# 12mPCIe.net
KiCad netlist of a schematic drawn in Altium Designer
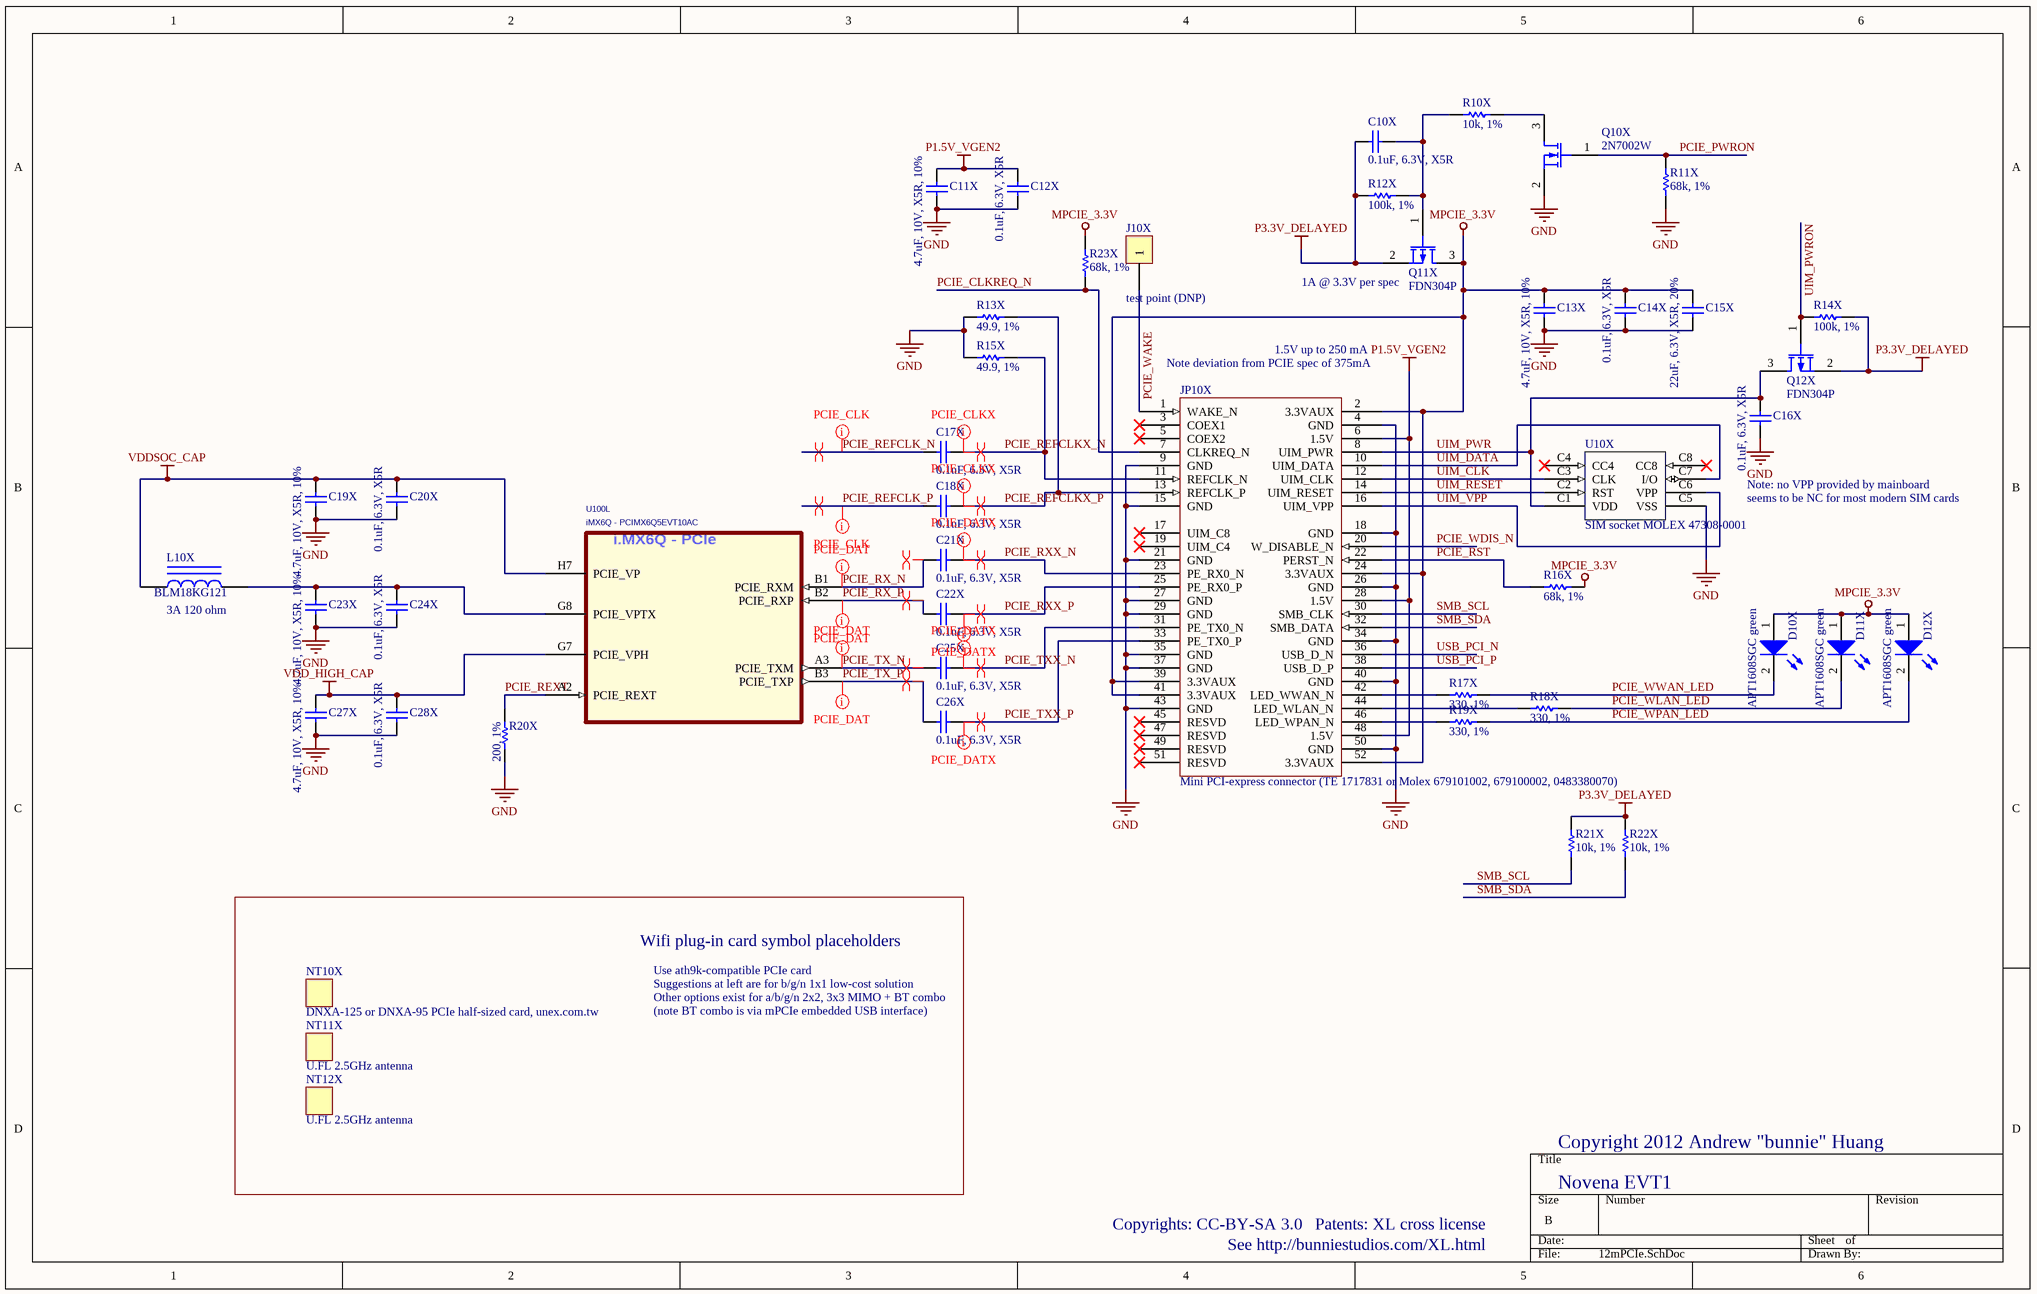
[diagram p0: 12mPCIe.SchDoc]

(export (version "E")
  (design (tool "Eeschema 10.0.6"))
  (components
    (comp (ref "C10X")
      (value "0.1uF, 6.3V, X5R")
      (footprint "CAPC0603N_B")
      (description "Capacitor (Semiconductor SIM Model)")
      (fields (field (name "PUBLISHER") "Altium Limited"))
      (libsource (lib "Miscellaneous Devices") (part "Cap Semi"))
    )
    (comp (ref "C11X")
      (value "4.7uF, 10V, X5R, 10%")
      (footprint "CAPC1608N")
      (description "Capacitor (Semiconductor SIM Model)")
      (fields (field (name "PUBLISHER") "Altium Limited"))
      (libsource (lib "Miscellaneous Devices") (part "Cap Semi"))
    )
    (comp (ref "C12X")
      (value "0.1uF, 6.3V, X5R")
      (footprint "CAPC0603N_B")
      (description "Capacitor (Semiconductor SIM Model)")
      (fields (field (name "PUBLISHER") "Altium Limited"))
      (libsource (lib "Miscellaneous Devices") (part "Cap Semi"))
    )
    (comp (ref "C13X")
      (value "4.7uF, 10V, X5R, 10%")
      (footprint "CAPC1608N")
      (description "Capacitor (Semiconductor SIM Model)")
      (fields (field (name "PUBLISHER") "Altium Limited"))
      (libsource (lib "Miscellaneous Devices") (part "Cap Semi"))
    )
    (comp (ref "C14X")
      (value "0.1uF, 6.3V, X5R")
      (footprint "CAPC0603N_B")
      (description "Capacitor (Semiconductor SIM Model)")
      (fields (field (name "PUBLISHER") "Altium Limited"))
      (libsource (lib "Miscellaneous Devices") (part "Cap Semi"))
    )
    (comp (ref "C15X")
      (value "22uF, 6.3V, X5R, 20%")
      (footprint "CAPC1608N_HD")
      (description "Capacitor (Semiconductor SIM Model)")
      (fields (field (name "PUBLISHER") "Altium Limited"))
      (libsource (lib "Miscellaneous Devices") (part "Cap Semi"))
    )
    (comp (ref "C16X")
      (value "0.1uF, 6.3V, X5R")
      (footprint "CAPC0603N_B")
      (description "Capacitor (Semiconductor SIM Model)")
      (fields (field (name "PUBLISHER") "Altium Limited"))
      (libsource (lib "Miscellaneous Devices") (part "Cap Semi"))
    )
    (comp (ref "C17X")
      (value "0.1uF, 6.3V, X5R")
      (footprint "CAPC0603N_B")
      (description "Capacitor (Semiconductor SIM Model)")
      (fields (field (name "PUBLISHER") "Altium Limited"))
      (libsource (lib "Miscellaneous Devices") (part "Cap Semi"))
    )
    (comp (ref "C18X")
      (value "0.1uF, 6.3V, X5R")
      (footprint "CAPC0603N_B")
      (description "Capacitor (Semiconductor SIM Model)")
      (fields (field (name "PUBLISHER") "Altium Limited"))
      (libsource (lib "Miscellaneous Devices") (part "Cap Semi"))
    )
    (comp (ref "C19X")
      (value "4.7uF, 10V, X5R, 10%")
      (footprint "CAPC1608N_HD")
      (description "Capacitor (Semiconductor SIM Model)")
      (fields (field (name "PUBLISHER") "Altium Limited"))
      (libsource (lib "Miscellaneous Devices") (part "Cap Semi"))
    )
    (comp (ref "C20X")
      (value "0.1uF, 6.3V, X5R")
      (footprint "CAPC0603N_B")
      (description "Capacitor (Semiconductor SIM Model)")
      (fields (field (name "PUBLISHER") "Altium Limited"))
      (libsource (lib "Miscellaneous Devices") (part "Cap Semi"))
    )
    (comp (ref "C21X")
      (value "0.1uF, 6.3V, X5R")
      (footprint "CAPC0603N_B")
      (description "Capacitor (Semiconductor SIM Model)")
      (fields (field (name "PUBLISHER") "Altium Limited"))
      (libsource (lib "Miscellaneous Devices") (part "Cap Semi"))
    )
    (comp (ref "C22X")
      (value "0.1uF, 6.3V, X5R")
      (footprint "CAPC0603N_B")
      (description "Capacitor (Semiconductor SIM Model)")
      (fields (field (name "PUBLISHER") "Altium Limited"))
      (libsource (lib "Miscellaneous Devices") (part "Cap Semi"))
    )
    (comp (ref "C23X")
      (value "4.7uF, 10V, X5R, 10%")
      (footprint "CAPC1608N_HD")
      (description "Capacitor (Semiconductor SIM Model)")
      (fields (field (name "PUBLISHER") "Altium Limited"))
      (libsource (lib "Miscellaneous Devices") (part "Cap Semi"))
    )
    (comp (ref "C24X")
      (value "0.1uF, 6.3V, X5R")
      (footprint "CAPC0603N_B")
      (description "Capacitor (Semiconductor SIM Model)")
      (fields (field (name "PUBLISHER") "Altium Limited"))
      (libsource (lib "Miscellaneous Devices") (part "Cap Semi"))
    )
    (comp (ref "C25X")
      (value "0.1uF, 6.3V, X5R")
      (footprint "CAPC0603N_B")
      (description "Capacitor (Semiconductor SIM Model)")
      (fields (field (name "PUBLISHER") "Altium Limited"))
      (libsource (lib "Miscellaneous Devices") (part "Cap Semi"))
    )
    (comp (ref "C26X")
      (value "0.1uF, 6.3V, X5R")
      (footprint "CAPC0603N_B")
      (description "Capacitor (Semiconductor SIM Model)")
      (fields (field (name "PUBLISHER") "Altium Limited"))
      (libsource (lib "Miscellaneous Devices") (part "Cap Semi"))
    )
    (comp (ref "C27X")
      (value "4.7uF, 10V, X5R, 10%")
      (footprint "CAPC1608N_HD")
      (description "Capacitor (Semiconductor SIM Model)")
      (fields (field (name "PUBLISHER") "Altium Limited"))
      (libsource (lib "Miscellaneous Devices") (part "Cap Semi"))
    )
    (comp (ref "C28X")
      (value "0.1uF, 6.3V, X5R")
      (footprint "CAPC0603N_B")
      (description "Capacitor (Semiconductor SIM Model)")
      (fields (field (name "PUBLISHER") "Altium Limited"))
      (libsource (lib "Miscellaneous Devices") (part "Cap Semi"))
    )
    (comp (ref "D10X")
      (value "APT1608SGC green")
      (footprint "CD1608-0603")
      (description "Typical RED, GREEN, YELLOW, AMBER GaAs LED")
      (fields (field (name "PUBLISHER") "Altium Limited"))
      (libsource (lib "Miscellaneous Devices") (part "LED2"))
    )
    (comp (ref "D11X")
      (value "APT1608SGC green")
      (footprint "CD1608-0603")
      (description "Typical RED, GREEN, YELLOW, AMBER GaAs LED")
      (fields (field (name "PUBLISHER") "Altium Limited"))
      (libsource (lib "Miscellaneous Devices") (part "LED2"))
    )
    (comp (ref "D12X")
      (value "APT1608SGC green")
      (footprint "CD1608-0603")
      (description "Typical RED, GREEN, YELLOW, AMBER GaAs LED")
      (fields (field (name "PUBLISHER") "Altium Limited"))
      (libsource (lib "Miscellaneous Devices") (part "LED2"))
    )
    (comp (ref "J10X")
      (value "test point (DNP)")
      (footprint "TP_SMT_38mil")
      (description "Connector")
      (libsource (lib "*") (part "CON1"))
    )
    (comp (ref "JP10X")
      (value "Mini PCI-express connector (TE 1717831 or Molex 679101002, 679100002, 0483380070)")
      (footprint "MPCI_FULL_TE_1717831")
      (description "Mini PCI-express, e.g. TE 1717831")
      (libsource (lib "commonsch") (part "MINI_PCIE"))
    )
    (comp (ref "L10X")
      (value "BLM18KG121")
      (footprint "INDC1608AN")
      (description "Magnetic-Core Inductor")
      (fields (field (name "ALTIUM_VALUE") "3A 120 ohm") (field (name "PUBLISHER") "Altium Limited"))
      (libsource (lib "Miscellaneous Devices") (part "Inductor Iron"))
    )
    (comp (ref "NT10X")
      (value "DNXA-125 or DNXA-95 PCIe half-sized card, unex.com.tw")
      (description "Placeholder for non-electrical BOM items")
      (libsource (lib "commonsch") (part "NOTE"))
    )
    (comp (ref "NT11X")
      (value "U.FL 2.5GHz antenna")
      (description "Placeholder for non-electrical BOM items")
      (libsource (lib "commonsch") (part "NOTE"))
    )
    (comp (ref "NT12X")
      (value "U.FL 2.5GHz antenna")
      (description "Placeholder for non-electrical BOM items")
      (libsource (lib "commonsch") (part "NOTE"))
    )
    (comp (ref "Q10X")
      (value "2N7002W")
      (footprint "SOT323-3AN")
      (description "N-Channel MOSFET")
      (fields (field (name "PUBLISHER") "Altium Limited"))
      (libsource (lib "Miscellaneous Devices") (part "MOSFET-N"))
    )
    (comp (ref "Q11X")
      (value "FDN304P")
      (footprint "SOT23-3N")
      (description "P-Channel MOSFET")
      (fields (field (name "PUBLISHER") "Altium Limited"))
      (libsource (lib "Miscellaneous Devices") (part "MOSFET-P"))
    )
    (comp (ref "Q12X")
      (value "FDN304P")
      (footprint "SOT23-3N")
      (description "P-Channel MOSFET")
      (fields (field (name "PUBLISHER") "Altium Limited"))
      (libsource (lib "Miscellaneous Devices") (part "MOSFET-P"))
    )
    (comp (ref "R10X")
      (value "10k, 1%")
      (footprint "RESC1005N")
      (description "Resistor")
      (fields (field (name "PUBLISHER") "Altium Limited"))
      (libsource (lib "Miscellaneous Devices") (part "Res1"))
    )
    (comp (ref "R11X")
      (value "68k, 1%")
      (footprint "RESC1005N")
      (description "Resistor")
      (fields (field (name "PUBLISHER") "Altium Limited"))
      (libsource (lib "Miscellaneous Devices") (part "Res1"))
    )
    (comp (ref "R12X")
      (value "100k, 1%")
      (footprint "RESC1005N")
      (description "Resistor")
      (fields (field (name "PUBLISHER") "Altium Limited"))
      (libsource (lib "Miscellaneous Devices") (part "Res1"))
    )
    (comp (ref "R13X")
      (value "49.9, 1%")
      (footprint "RESC1005N")
      (description "Resistor")
      (fields (field (name "PUBLISHER") "Altium Limited"))
      (libsource (lib "Miscellaneous Devices") (part "Res1"))
    )
    (comp (ref "R14X")
      (value "100k, 1%")
      (footprint "RESC1005N")
      (description "Resistor")
      (fields (field (name "PUBLISHER") "Altium Limited"))
      (libsource (lib "Miscellaneous Devices") (part "Res1"))
    )
    (comp (ref "R15X")
      (value "49.9, 1%")
      (footprint "RESC1005N")
      (description "Resistor")
      (fields (field (name "PUBLISHER") "Altium Limited"))
      (libsource (lib "Miscellaneous Devices") (part "Res1"))
    )
    (comp (ref "R16X")
      (value "68k, 1%")
      (footprint "RESC1005N")
      (description "Resistor")
      (fields (field (name "PUBLISHER") "Altium Limited"))
      (libsource (lib "Miscellaneous Devices") (part "Res1"))
    )
    (comp (ref "R17X")
      (value "330, 1%")
      (footprint "RESC1005N")
      (description "Resistor")
      (fields (field (name "PUBLISHER") "Altium Limited"))
      (libsource (lib "Miscellaneous Devices") (part "Res1"))
    )
    (comp (ref "R18X")
      (value "330, 1%")
      (footprint "RESC1005N")
      (description "Resistor")
      (fields (field (name "PUBLISHER") "Altium Limited"))
      (libsource (lib "Miscellaneous Devices") (part "Res1"))
    )
    (comp (ref "R19X")
      (value "330, 1%")
      (footprint "RESC1005N")
      (description "Resistor")
      (fields (field (name "PUBLISHER") "Altium Limited"))
      (libsource (lib "Miscellaneous Devices") (part "Res1"))
    )
    (comp (ref "R20X")
      (value "200, 1%")
      (footprint "RESC1005N")
      (description "Resistor")
      (fields (field (name "PUBLISHER") "Altium Limited"))
      (libsource (lib "Miscellaneous Devices") (part "Res1"))
    )
    (comp (ref "R21X")
      (value "10k, 1%")
      (footprint "RESC1005N")
      (description "Resistor")
      (fields (field (name "PUBLISHER") "Altium Limited"))
      (libsource (lib "Miscellaneous Devices") (part "Res1"))
    )
    (comp (ref "R22X")
      (value "10k, 1%")
      (footprint "RESC1005N")
      (description "Resistor")
      (fields (field (name "PUBLISHER") "Altium Limited"))
      (libsource (lib "Miscellaneous Devices") (part "Res1"))
    )
    (comp (ref "R23X")
      (value "68k, 1%")
      (footprint "RESC1005N")
      (description "Resistor")
      (fields (field (name "PUBLISHER") "Altium Limited"))
      (libsource (lib "Miscellaneous Devices") (part "Res1"))
    )
    (comp (ref "U10X")
      (value "SIM socket MOLEX 47308-0001")
      (footprint "MOLEX_SIM_47308-001")
      (description "ISO 7816 SIM card socket")
      (libsource (lib "commonsch") (part "ISO7816 (SIM card)"))
    )
    (comp (ref "U100")
      (value "iMX6Q - PCIMX6Q5EVT10AC")
      (description "PLACEHOLDER FOR FREESCALE PART NUMBER PMCIMX6Q6VV1A.")
      (libsource (lib "*") (part "PCIMX6Q6VV1A"))
    )
  )
  (nets
    (net (code "1") (name "/PCIE_CLKREQ_N") (class "Default")
      (node (ref "JP10X") (pin "7") (pinfunction "CLKREQ_N_7") (pintype "passive"))
      (node (ref "R23X") (pin "1") (pinfunction "1_1") (pintype "passive"))
    )
    (net (code "2") (name "/PCIE_PWRON") (class "Default")
      (node (ref "Q10X") (pin "1") (pinfunction "G_1") (pintype "passive"))
      (node (ref "R11X") (pin "1") (pinfunction "1_1") (pintype "passive"))
    )
    (net (code "3") (name "/PCIE_REFCLKX_N") (class "Default")
      (node (ref "C17X") (pin "1") (pinfunction "1_1") (pintype "passive"))
      (node (ref "JP10X") (pin "11") (pinfunction "REFCLK_N_11") (pintype "input"))
      (node (ref "R15X") (pin "1") (pinfunction "1_1") (pintype "passive"))
    )
    (net (code "4") (name "/PCIE_REFCLKX_P") (class "Default")
      (node (ref "C18X") (pin "1") (pinfunction "1_1") (pintype "passive"))
      (node (ref "JP10X") (pin "13") (pinfunction "REFCLK_P_13") (pintype "input"))
      (node (ref "R13X") (pin "1") (pinfunction "1_1") (pintype "passive"))
    )
    (net (code "5") (name "/PCIE_REFCLK_N") (class "Default")
      (node (ref "C17X") (pin "2") (pinfunction "2_2") (pintype "passive"))
    )
    (net (code "6") (name "/PCIE_REFCLK_P") (class "Default")
      (node (ref "C18X") (pin "2") (pinfunction "2_2") (pintype "passive"))
    )
    (net (code "7") (name "/PCIE_REXT") (class "Default")
      (node (ref "R20X") (pin "2") (pinfunction "2_2") (pintype "passive"))
      (node (ref "U100") (pin "A2") (pinfunction "PCIE_REXT_A2") (pintype "input"))
    )
    (net (code "8") (name "/PCIE_RST") (class "Default")
      (node (ref "JP10X") (pin "22") (pinfunction "PERST_N_22") (pintype "input"))
      (node (ref "R16X") (pin "2") (pinfunction "2_2") (pintype "passive"))
    )
    (net (code "9") (name "/PCIE_RXX_N") (class "Default")
      (node (ref "C21X") (pin "1") (pinfunction "1_1") (pintype "passive"))
      (node (ref "JP10X") (pin "23") (pinfunction "PE_RX0_N_23") (pintype "passive"))
    )
    (net (code "10") (name "/PCIE_RXX_P") (class "Default")
      (node (ref "C22X") (pin "1") (pinfunction "1_1") (pintype "passive"))
      (node (ref "JP10X") (pin "25") (pinfunction "PE_RX0_P_25") (pintype "passive"))
    )
    (net (code "11") (name "/PCIE_RX_N") (class "Default")
      (node (ref "C21X") (pin "2") (pinfunction "2_2") (pintype "passive"))
      (node (ref "U100") (pin "B1") (pinfunction "PCIE_RXM_B1") (pintype "input"))
    )
    (net (code "12") (name "/PCIE_RX_P") (class "Default")
      (node (ref "C22X") (pin "2") (pinfunction "2_2") (pintype "passive"))
      (node (ref "U100") (pin "B2") (pinfunction "PCIE_RXP_B2") (pintype "input"))
    )
    (net (code "13") (name "/PCIE_TXX_N") (class "Default")
      (node (ref "C25X") (pin "1") (pinfunction "1_1") (pintype "passive"))
      (node (ref "JP10X") (pin "31") (pinfunction "PE_TX0_N_31") (pintype "passive"))
    )
    (net (code "14") (name "/PCIE_TXX_P") (class "Default")
      (node (ref "C26X") (pin "1") (pinfunction "1_1") (pintype "passive"))
      (node (ref "JP10X") (pin "33") (pinfunction "PE_TX0_P_33") (pintype "passive"))
    )
    (net (code "15") (name "/PCIE_TX_N") (class "Default")
      (node (ref "C25X") (pin "2") (pinfunction "2_2") (pintype "passive"))
      (node (ref "U100") (pin "A3") (pinfunction "PCIE_TXM_A3") (pintype "output"))
    )
    (net (code "16") (name "/PCIE_TX_P") (class "Default")
      (node (ref "C26X") (pin "2") (pinfunction "2_2") (pintype "passive"))
      (node (ref "U100") (pin "B3") (pinfunction "PCIE_TXP_B3") (pintype "output"))
    )
    (net (code "17") (name "/PCIE_WAKE") (class "Default")
      (node (ref "J10X") (pin "1") (pinfunction "1_1") (pintype "passive"))
      (node (ref "JP10X") (pin "1") (pinfunction "WAKE_N_1") (pintype "input"))
    )
    (net (code "18") (name "/PCIE_WDIS_N") (class "Default")
      (node (ref "JP10X") (pin "20") (pinfunction "W_DISABLE_N_20") (pintype "input"))
    )
    (net (code "19") (name "/PCIE_WLAN_LED") (class "Default")
      (node (ref "D11X") (pin "2") (pinfunction "K_2") (pintype "passive"))
      (node (ref "R18X") (pin "2") (pinfunction "2_2") (pintype "passive"))
    )
    (net (code "20") (name "/PCIE_WPAN_LED") (class "Default")
      (node (ref "D12X") (pin "2") (pinfunction "K_2") (pintype "passive"))
      (node (ref "R19X") (pin "2") (pinfunction "2_2") (pintype "passive"))
    )
    (net (code "21") (name "/PCIE_WWAN_LED") (class "Default")
      (node (ref "D10X") (pin "2") (pinfunction "K_2") (pintype "passive"))
      (node (ref "R17X") (pin "2") (pinfunction "2_2") (pintype "passive"))
    )
    (net (code "22") (name "/SMB_SCL") (class "Default")
      (node (ref "JP10X") (pin "30") (pinfunction "SMB_CLK_30") (pintype "input"))
      (node (ref "R21X") (pin "1") (pinfunction "1_1") (pintype "passive"))
    )
    (net (code "23") (name "/SMB_SDA") (class "Default")
      (node (ref "JP10X") (pin "32") (pinfunction "SMB_DATA_32") (pintype "input"))
      (node (ref "R22X") (pin "1") (pinfunction "1_1") (pintype "passive"))
    )
    (net (code "24") (name "/UIM_CLK") (class "Default")
      (node (ref "JP10X") (pin "12") (pinfunction "UIM_CLK_12") (pintype "passive"))
      (node (ref "U10X") (pin "C3") (pinfunction "CLK_C3") (pintype "input"))
    )
    (net (code "25") (name "/UIM_DATA") (class "Default")
      (node (ref "JP10X") (pin "10") (pinfunction "UIM_DATA_10") (pintype "passive"))
      (node (ref "U10X") (pin "C7") (pinfunction "I/O_C7") (pintype "bidirectional"))
    )
    (net (code "26") (name "/UIM_PWR") (class "Default")
      (node (ref "C16X") (pin "1") (pinfunction "1_1") (pintype "passive"))
      (node (ref "JP10X") (pin "8") (pinfunction "UIM_PWR_8") (pintype "passive"))
      (node (ref "Q12X") (pin "3") (pinfunction "D_3") (pintype "passive"))
      (node (ref "U10X") (pin "C1") (pinfunction "VDD_C1") (pintype "power_in"))
    )
    (net (code "27") (name "/UIM_PWRON") (class "Default")
      (node (ref "Q12X") (pin "1") (pinfunction "G_1") (pintype "passive"))
      (node (ref "R14X") (pin "2") (pinfunction "2_2") (pintype "passive"))
    )
    (net (code "28") (name "/UIM_RESET") (class "Default")
      (node (ref "JP10X") (pin "14") (pinfunction "UIM_RESET_14") (pintype "passive"))
      (node (ref "U10X") (pin "C2") (pinfunction "RST_C2") (pintype "input"))
    )
    (net (code "29") (name "/UIM_VPP") (class "Default")
      (node (ref "JP10X") (pin "16") (pinfunction "UIM_VPP_16") (pintype "passive"))
      (node (ref "U10X") (pin "C6") (pinfunction "VPP_C6") (pintype "power_in"))
    )
    (net (code "30") (name "/USB_PCI_N") (class "Default")
      (node (ref "JP10X") (pin "36") (pinfunction "USB_D_N_36") (pintype "passive"))
    )
    (net (code "31") (name "/USB_PCI_P") (class "Default")
      (node (ref "JP10X") (pin "38") (pinfunction "USB_D_P_38") (pintype "passive"))
    )
    (net (code "32") (name "GND") (class "Default")
      (node (ref "C11X") (pin "2") (pinfunction "2_2") (pintype "passive"))
      (node (ref "C12X") (pin "2") (pinfunction "2_2") (pintype "passive"))
      (node (ref "C13X") (pin "2") (pinfunction "2_2") (pintype "passive"))
      (node (ref "C14X") (pin "2") (pinfunction "2_2") (pintype "passive"))
      (node (ref "C15X") (pin "2") (pinfunction "2_2") (pintype "passive"))
      (node (ref "C16X") (pin "2") (pinfunction "2_2") (pintype "passive"))
      (node (ref "C19X") (pin "2") (pinfunction "2_2") (pintype "passive"))
      (node (ref "C20X") (pin "2") (pinfunction "2_2") (pintype "passive"))
      (node (ref "C23X") (pin "2") (pinfunction "2_2") (pintype "passive"))
      (node (ref "C24X") (pin "2") (pinfunction "2_2") (pintype "passive"))
      (node (ref "C27X") (pin "2") (pinfunction "2_2") (pintype "passive"))
      (node (ref "C28X") (pin "2") (pinfunction "2_2") (pintype "passive"))
      (node (ref "JP10X") (pin "15") (pinfunction "GND_15") (pintype "power_in"))
      (node (ref "JP10X") (pin "18") (pinfunction "GND_18") (pintype "power_in"))
      (node (ref "JP10X") (pin "21") (pinfunction "GND_21") (pintype "power_in"))
      (node (ref "JP10X") (pin "26") (pinfunction "GND_26") (pintype "power_in"))
      (node (ref "JP10X") (pin "27") (pinfunction "GND_27") (pintype "power_in"))
      (node (ref "JP10X") (pin "29") (pinfunction "GND_29") (pintype "power_in"))
      (node (ref "JP10X") (pin "34") (pinfunction "GND_34") (pintype "power_in"))
      (node (ref "JP10X") (pin "35") (pinfunction "GND_35") (pintype "power_in"))
      (node (ref "JP10X") (pin "37") (pinfunction "GND_37") (pintype "power_in"))
      (node (ref "JP10X") (pin "4") (pinfunction "GND_4") (pintype "power_in"))
      (node (ref "JP10X") (pin "40") (pinfunction "GND_40") (pintype "power_in"))
      (node (ref "JP10X") (pin "43") (pinfunction "GND_43") (pintype "power_in"))
      (node (ref "JP10X") (pin "50") (pinfunction "GND_50") (pintype "power_in"))
      (node (ref "JP10X") (pin "9") (pinfunction "GND_9") (pintype "power_in"))
      (node (ref "Q10X") (pin "2") (pinfunction "S_2") (pintype "passive"))
      (node (ref "R11X") (pin "2") (pinfunction "2_2") (pintype "passive"))
      (node (ref "R13X") (pin "2") (pinfunction "2_2") (pintype "passive"))
      (node (ref "R15X") (pin "2") (pinfunction "2_2") (pintype "passive"))
      (node (ref "R20X") (pin "1") (pinfunction "1_1") (pintype "passive"))
      (node (ref "U10X") (pin "C5") (pinfunction "VSS_C5") (pintype "power_in"))
    )
    (net (code "33") (name "MPCIE_3.3V") (class "Default")
      (node (ref "C13X") (pin "1") (pinfunction "1_1") (pintype "passive"))
      (node (ref "C14X") (pin "1") (pinfunction "1_1") (pintype "passive"))
      (node (ref "C15X") (pin "1") (pinfunction "1_1") (pintype "passive"))
      (node (ref "D10X") (pin "1") (pinfunction "A_1") (pintype "passive"))
      (node (ref "D11X") (pin "1") (pinfunction "A_1") (pintype "passive"))
      (node (ref "D12X") (pin "1") (pinfunction "A_1") (pintype "passive"))
      (node (ref "JP10X") (pin "2") (pinfunction "3.3VAUX_2") (pintype "power_in"))
      (node (ref "JP10X") (pin "24") (pinfunction "3.3VAUX_24") (pintype "power_in"))
      (node (ref "JP10X") (pin "39") (pinfunction "3.3VAUX_39") (pintype "power_in"))
      (node (ref "JP10X") (pin "41") (pinfunction "3.3VAUX_41") (pintype "power_in"))
      (node (ref "JP10X") (pin "52") (pinfunction "3.3VAUX_52") (pintype "power_in"))
      (node (ref "Q11X") (pin "3") (pinfunction "D_3") (pintype "passive"))
      (node (ref "R16X") (pin "1") (pinfunction "1_1") (pintype "passive"))
      (node (ref "R23X") (pin "2") (pinfunction "2_2") (pintype "passive"))
    )
    (net (code "34") (name "Net-(JP10X-LED_WLAN_N)") (class "Default")
      (node (ref "JP10X") (pin "44") (pinfunction "LED_WLAN_N_44") (pintype "passive"))
      (node (ref "R18X") (pin "1") (pinfunction "1_1") (pintype "passive"))
    )
    (net (code "35") (name "Net-(JP10X-LED_WPAN_N)") (class "Default")
      (node (ref "JP10X") (pin "46") (pinfunction "LED_WPAN_N_46") (pintype "passive"))
      (node (ref "R19X") (pin "1") (pinfunction "1_1") (pintype "passive"))
    )
    (net (code "36") (name "Net-(JP10X-LED_WWAN_N)") (class "Default")
      (node (ref "JP10X") (pin "42") (pinfunction "LED_WWAN_N_42") (pintype "passive"))
      (node (ref "R17X") (pin "1") (pinfunction "1_1") (pintype "passive"))
    )
    (net (code "37") (name "Net-(Q10X-D)") (class "Default")
      (node (ref "Q10X") (pin "3") (pinfunction "D_3") (pintype "passive"))
      (node (ref "R10X") (pin "2") (pinfunction "2_2") (pintype "passive"))
    )
    (net (code "38") (name "Net-(Q11X-G)") (class "Default")
      (node (ref "C10X") (pin "1") (pinfunction "1_1") (pintype "passive"))
      (node (ref "Q11X") (pin "1") (pinfunction "G_1") (pintype "passive"))
      (node (ref "R10X") (pin "1") (pinfunction "1_1") (pintype "passive"))
      (node (ref "R12X") (pin "1") (pinfunction "1_1") (pintype "passive"))
    )
    (net (code "39") (name "Net-(U100L-PCIE_VPTX)") (class "Default")
      (node (ref "C23X") (pin "1") (pinfunction "1_1") (pintype "passive"))
      (node (ref "C24X") (pin "1") (pinfunction "1_1") (pintype "passive"))
      (node (ref "L10X") (pin "2") (pinfunction "2_2") (pintype "passive"))
      (node (ref "U100") (pin "G8") (pinfunction "PCIE_VPTX_G8") (pintype "power_in"))
    )
    (net (code "40") (name "P1.5V_VGEN2") (class "Default")
      (node (ref "C11X") (pin "1") (pinfunction "1_1") (pintype "passive"))
      (node (ref "C12X") (pin "1") (pinfunction "1_1") (pintype "passive"))
      (node (ref "JP10X") (pin "28") (pinfunction "1.5V_28") (pintype "power_in"))
      (node (ref "JP10X") (pin "48") (pinfunction "1.5V_48") (pintype "power_in"))
      (node (ref "JP10X") (pin "6") (pinfunction "1.5V_6") (pintype "power_in"))
    )
    (net (code "41") (name "P3.3V_DELAYED") (class "Default")
      (node (ref "C10X") (pin "2") (pinfunction "2_2") (pintype "passive"))
      (node (ref "Q11X") (pin "2") (pinfunction "S_2") (pintype "passive"))
      (node (ref "Q12X") (pin "2") (pinfunction "S_2") (pintype "passive"))
      (node (ref "R12X") (pin "2") (pinfunction "2_2") (pintype "passive"))
      (node (ref "R14X") (pin "1") (pinfunction "1_1") (pintype "passive"))
      (node (ref "R21X") (pin "2") (pinfunction "2_2") (pintype "passive"))
      (node (ref "R22X") (pin "2") (pinfunction "2_2") (pintype "passive"))
    )
    (net (code "42") (name "VDDSOC_CAP") (class "Default")
      (node (ref "C19X") (pin "1") (pinfunction "1_1") (pintype "passive"))
      (node (ref "C20X") (pin "1") (pinfunction "1_1") (pintype "passive"))
      (node (ref "L10X") (pin "1") (pinfunction "1_1") (pintype "passive"))
      (node (ref "U100") (pin "H7") (pinfunction "PCIE_VP_H7") (pintype "power_in"))
    )
    (net (code "43") (name "VDD_HIGH_CAP") (class "Default")
      (node (ref "C27X") (pin "1") (pinfunction "1_1") (pintype "passive"))
      (node (ref "C28X") (pin "1") (pinfunction "1_1") (pintype "passive"))
      (node (ref "U100") (pin "G7") (pinfunction "PCIE_VPH_G7") (pintype "power_in"))
    )
    (net (code "44") (name "unconnected-(JP10X-COEX1-Pad3)") (class "Default")
      (node (ref "JP10X") (pin "3") (pinfunction "COEX1_3") (pintype "passive+no_connect"))
    )
    (net (code "45") (name "unconnected-(JP10X-COEX2-Pad5)") (class "Default")
      (node (ref "JP10X") (pin "5") (pinfunction "COEX2_5") (pintype "passive+no_connect"))
    )
    (net (code "46") (name "unconnected-(JP10X-RESVD-Pad45)") (class "Default")
      (node (ref "JP10X") (pin "45") (pinfunction "RESVD_45") (pintype "passive+no_connect"))
    )
    (net (code "47") (name "unconnected-(JP10X-RESVD-Pad47)") (class "Default")
      (node (ref "JP10X") (pin "47") (pinfunction "RESVD_47") (pintype "passive+no_connect"))
    )
    (net (code "48") (name "unconnected-(JP10X-RESVD-Pad49)") (class "Default")
      (node (ref "JP10X") (pin "49") (pinfunction "RESVD_49") (pintype "passive+no_connect"))
    )
    (net (code "49") (name "unconnected-(JP10X-RESVD-Pad51)") (class "Default")
      (node (ref "JP10X") (pin "51") (pinfunction "RESVD_51") (pintype "passive+no_connect"))
    )
    (net (code "50") (name "unconnected-(JP10X-UIM_C4-Pad19)") (class "Default")
      (node (ref "JP10X") (pin "19") (pinfunction "UIM_C4_19") (pintype "passive+no_connect"))
    )
    (net (code "51") (name "unconnected-(JP10X-UIM_C8-Pad17)") (class "Default")
      (node (ref "JP10X") (pin "17") (pinfunction "UIM_C8_17") (pintype "passive+no_connect"))
    )
    (net (code "52") (name "unconnected-(U10X-CC4-PadC4)") (class "Default")
      (node (ref "U10X") (pin "C4") (pinfunction "CC4_C4") (pintype "input+no_connect"))
    )
    (net (code "53") (name "unconnected-(U10X-CC8-PadC8)") (class "Default")
      (node (ref "U10X") (pin "C8") (pinfunction "CC8_C8") (pintype "input+no_connect"))
    )
  )
)
